# OL_sensor.net
KiCad netlist of a schematic drawn in Altium Designer
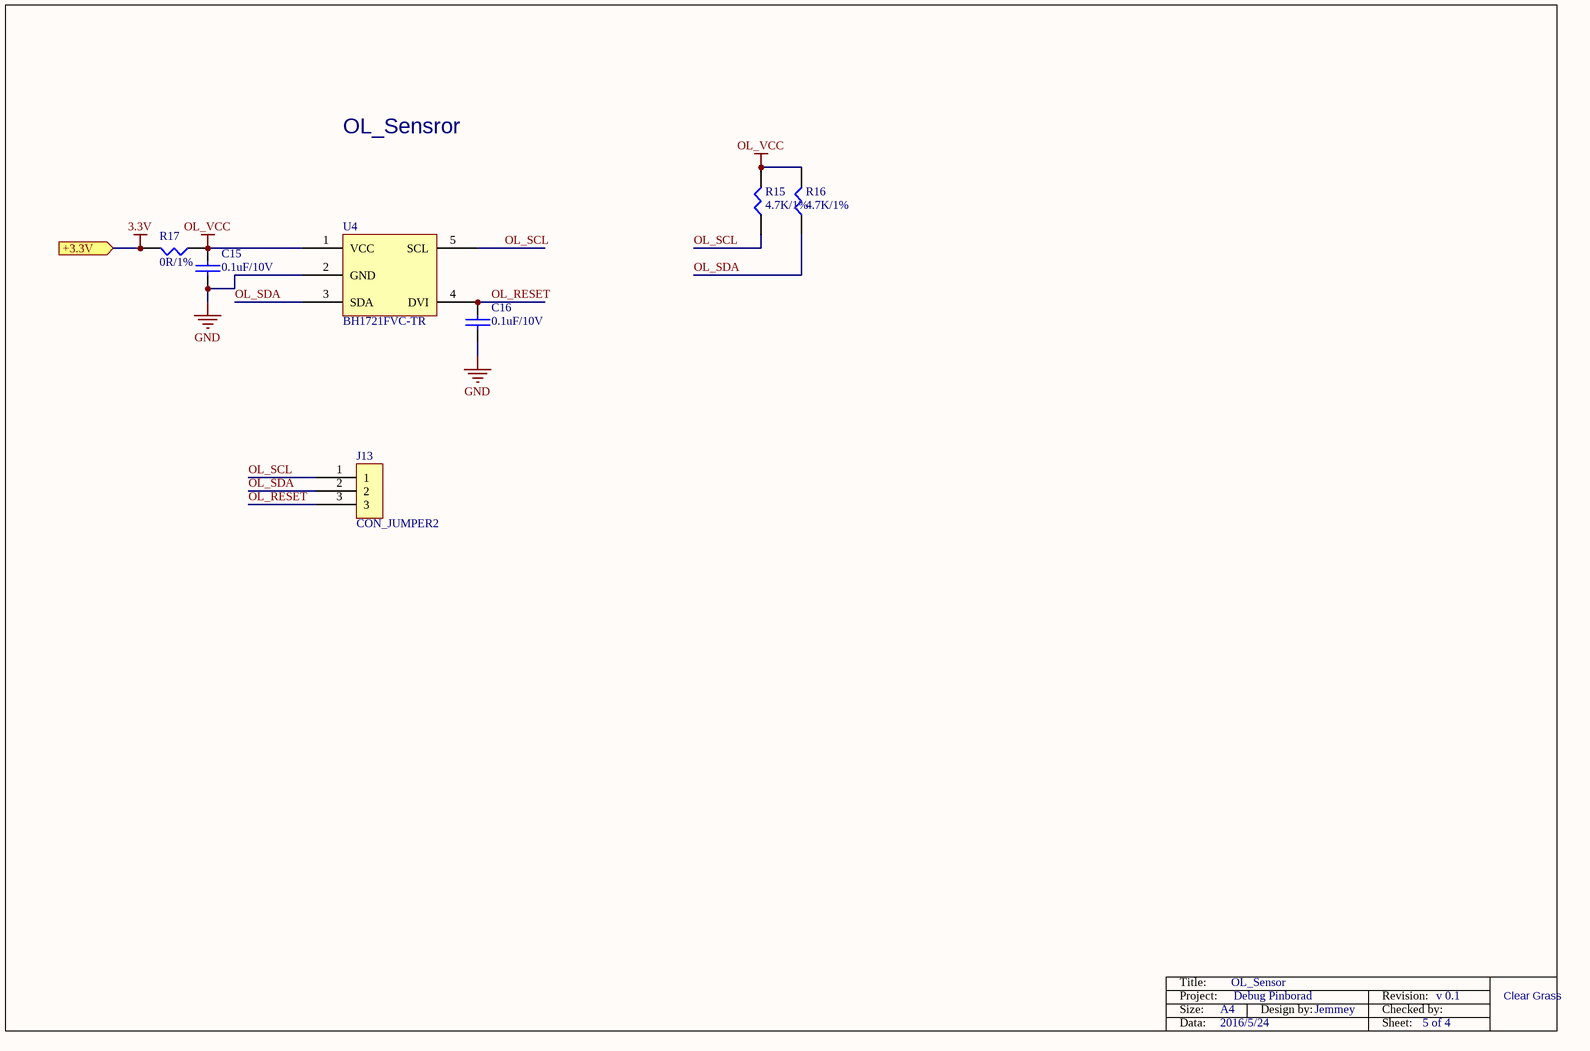
[diagram p0: OL_sensor.SchDoc]

(export (version "E")
  (design (tool "Eeschema 10.0.6"))
  (components
    (comp (ref "C15")
      (value "0.1uF/10V")
      (footprint "0402C")
      (description "厂家：Murata，型号：")
      (libsource (lib "*") (part "CAP"))
    )
    (comp (ref "C16")
      (value "0.1uF/10V")
      (footprint "0402C")
      (description "厂家：Murata，型号：")
      (libsource (lib "*") (part "CAP"))
    )
    (comp (ref "J13") (value "CON_JUMPER2") (libsource (lib "Debug Pinborad") (part "CON_JUMPER2")))
    (comp (ref "R15")
      (value "4.7K/1%")
      (footprint "0402R")
      (description "厂家：Yageo，型号：RC0402FR-0710KL")
      (libsource (lib "*") (part "RES1"))
    )
    (comp (ref "R16")
      (value "4.7K/1%")
      (footprint "0402R")
      (description "厂家：Yageo，型号：RC0402FR-0710KL")
      (libsource (lib "*") (part "RES1"))
    )
    (comp (ref "R17")
      (value "0R/1%")
      (footprint "0402R")
      (description "厂家：Yageo，型号：RC0402FR-0710KL")
      (libsource (lib "*") (part "RES1"))
    )
    (comp (ref "U4")
      (value "BH1721FVC-TR")
      (footprint "WSOF5")
      (libsource (lib "Schlib1") (part "BH1721FVC-TR"))
    )
  )
  (nets
    (net (code "1") (name "/OL_RESET") (class "Default")
      (node (ref "C16") (pin "1") (pinfunction "1_1") (pintype "passive"))
      (node (ref "J13") (pin "3") (pinfunction "3_3") (pintype "passive"))
      (node (ref "U4") (pin "4") (pinfunction "DVI_4") (pintype "passive"))
    )
    (net (code "2") (name "/OL_SCL") (class "Default")
      (node (ref "J13") (pin "1") (pinfunction "1_1") (pintype "passive"))
      (node (ref "R15") (pin "1") (pinfunction "1_1") (pintype "passive"))
      (node (ref "U4") (pin "5") (pinfunction "SCL_5") (pintype "passive"))
    )
    (net (code "3") (name "/OL_SDA") (class "Default")
      (node (ref "J13") (pin "2") (pinfunction "2_2") (pintype "passive"))
      (node (ref "R16") (pin "1") (pinfunction "1_1") (pintype "passive"))
      (node (ref "U4") (pin "3") (pinfunction "SDA_3") (pintype "passive"))
    )
    (net (code "4") (name "3.3V") (class "Default")
      (node (ref "R17") (pin "2") (pinfunction "2_2") (pintype "passive"))
    )
    (net (code "5") (name "GND") (class "Default")
      (node (ref "C15") (pin "2") (pinfunction "2_2") (pintype "passive"))
      (node (ref "C16") (pin "2") (pinfunction "2_2") (pintype "passive"))
      (node (ref "U4") (pin "2") (pinfunction "GND_2") (pintype "passive"))
    )
    (net (code "6") (name "OL_VCC") (class "Default")
      (node (ref "C15") (pin "1") (pinfunction "1_1") (pintype "passive"))
      (node (ref "R15") (pin "2") (pinfunction "2_2") (pintype "passive"))
      (node (ref "R16") (pin "2") (pinfunction "2_2") (pintype "passive"))
      (node (ref "R17") (pin "1") (pinfunction "1_1") (pintype "passive"))
      (node (ref "U4") (pin "1") (pinfunction "VCC_1") (pintype "passive"))
    )
  )
)
